# Sunfish_ECU_MotorFilter_RevA.net
KiCad netlist of a schematic drawn in Altium Designer
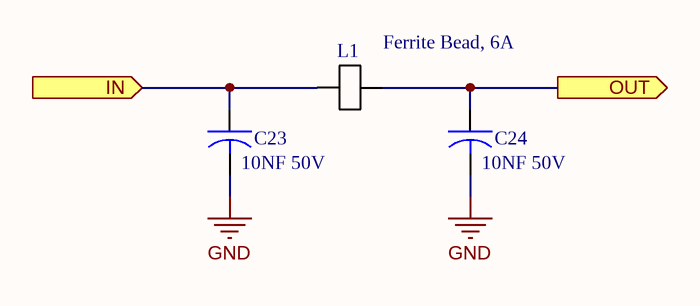
[diagram p0: Sunfish_ECU_MotorFilter_RevA.SchDoc]

(export (version "E")
  (design (tool "Eeschema 10.0.6"))
  (components
    (comp (ref "C23")
      (value "10NF 50V")
      (footprint "0603")
      (description "CAP CER 10NF 50V 10% X7R 0603")
      (fields (field (name "MANUFACTURER") "Murata"))
      (libsource (lib "Regulators") (part "CAP_10NF_50V_10%_0603"))
    )
    (comp (ref "C24")
      (value "10NF 50V")
      (footprint "0603")
      (description "CAP CER 10NF 50V 10% X7R 0603")
      (fields (field (name "MANUFACTURER") "Murata"))
      (libsource (lib "Regulators") (part "CAP_10NF_50V_10%_0603"))
    )
    (comp (ref "L1")
      (value "Ferrite Bead, 6A")
      (footprint "1806")
      (fields (field (name "MANUFACTURER") "MURATA"))
      (libsource (lib "Inductors") (part "IND_FERRITE_ BLM41PG600SN1L"))
    )
  )
  (nets
    (net (code "1") (name "/IN") (class "Default")
      (node (ref "C23") (pin "1") (pinfunction "1_1") (pintype "passive"))
      (node (ref "L1") (pin "1") (pinfunction "1_1") (pintype "passive"))
    )
    (net (code "2") (name "/OUT") (class "Default")
      (node (ref "C24") (pin "1") (pinfunction "1_1") (pintype "passive"))
      (node (ref "L1") (pin "2") (pinfunction "2_2") (pintype "passive"))
    )
    (net (code "3") (name "GND") (class "Default")
      (node (ref "C23") (pin "2") (pinfunction "2_2") (pintype "passive"))
      (node (ref "C24") (pin "2") (pinfunction "2_2") (pintype "passive"))
    )
  )
)
